# LDO_Schematic.net
KiCad netlist of a schematic drawn in Altium Designer
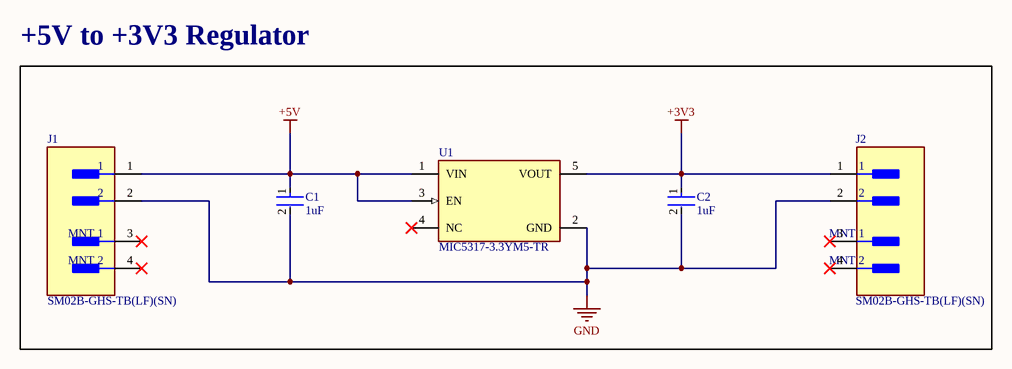
[diagram p0: LDO_Schematic.SchDoc]

(export (version "E")
  (design (tool "Eeschema 10.0.6"))
  (components
    (comp (ref "C1")
      (value "1uF")
      (footprint "FP-CC0805-0_85-MFG")
      (description "CAP CER 1UF 10V X7R 0805")
      (fields
        (field (name "MANUFACTURER") "Yageo")
        (field (name "OCTOPART") "https://octopart.com/cc0805kkx7r6bb105-yageo-42522859")
      )
      (libsource (lib "Altium Content Vault") (part "11868f565c42a9108669ba33697ecf6"))
    )
    (comp (ref "C2")
      (value "1uF")
      (footprint "FP-CC0805-0_85-MFG")
      (description "CAP CER 1UF 10V X7R 0805")
      (fields
        (field (name "MANUFACTURER") "Yageo")
        (field (name "OCTOPART") "https://octopart.com/cc0805kkx7r6bb105-yageo-42522859")
      )
      (libsource (lib "Altium Content Vault") (part "11868f565c42a9108669ba33697ecf6"))
    )
    (comp (ref "J1")
      (value "SM02B-GHS-TB(LF)(SN)")
      (footprint "FP-SM02B-GHS-TB_LF_SN-MFG")
      (description "CONN HEADER SMD R/A 2POS 1.25MM")
      (libsource (lib "") (part "56ec3178a87b3978bdc1b3682cd516a_1"))
    )
    (comp (ref "J2")
      (value "SM02B-GHS-TB(LF)(SN)")
      (footprint "FP-SM02B-GHS-TB_LF_SN-MFG")
      (description "CONN HEADER SMD R/A 2POS 1.25MM")
      (libsource (lib "Altium Content Vault") (part "56ec3178a87b3978bdc1b3682cd516a"))
    )
    (comp (ref "U1")
      (value "MIC5317-3.3YM5-TR")
      (footprint "FP-SOT23-5LD-PL-1-MFG")
      (description "IC REG LINEAR 3.3V 150MA SOT23-5")
      (libsource (lib "Altium Content Vault") (part "0a093dae7315cdc977fd108dde87457"))
    )
  )
  (nets
    (net (code "1") (name "+3V3") (class "Default")
      (node (ref "C2") (pin "1") (pinfunction "1_1") (pintype "passive"))
      (node (ref "J2") (pin "1") (pinfunction "1_1") (pintype "passive"))
      (node (ref "U1") (pin "5") (pinfunction "VOUT_5") (pintype "power_in"))
    )
    (net (code "2") (name "+5V") (class "Default")
      (node (ref "C1") (pin "1") (pinfunction "1_1") (pintype "passive"))
      (node (ref "J1") (pin "1") (pinfunction "1_1") (pintype "passive"))
      (node (ref "U1") (pin "1") (pinfunction "VIN_1") (pintype "power_in"))
      (node (ref "U1") (pin "3") (pinfunction "EN_3") (pintype "input"))
    )
    (net (code "3") (name "GND") (class "Default")
      (node (ref "C1") (pin "2") (pinfunction "2_2") (pintype "passive"))
      (node (ref "C2") (pin "2") (pinfunction "2_2") (pintype "passive"))
      (node (ref "J1") (pin "2") (pinfunction "2_2") (pintype "passive"))
      (node (ref "J2") (pin "2") (pinfunction "2_2") (pintype "passive"))
      (node (ref "U1") (pin "2") (pinfunction "GND_2") (pintype "power_in"))
    )
    (net (code "4") (name "unconnected-(J1-MNT_1-Pad3)") (class "Default")
      (node (ref "J1") (pin "3") (pinfunction "MNT_1_3") (pintype "passive+no_connect"))
    )
    (net (code "5") (name "unconnected-(J1-MNT_2-Pad4)") (class "Default")
      (node (ref "J1") (pin "4") (pinfunction "MNT_2_4") (pintype "passive+no_connect"))
    )
    (net (code "6") (name "unconnected-(J2-MNT_1-Pad3)") (class "Default")
      (node (ref "J2") (pin "3") (pinfunction "MNT_1_3") (pintype "passive+no_connect"))
    )
    (net (code "7") (name "unconnected-(J2-MNT_2-Pad4)") (class "Default")
      (node (ref "J2") (pin "4") (pinfunction "MNT_2_4") (pintype "passive+no_connect"))
    )
    (net (code "8") (name "unconnected-(U1-NC-Pad4)") (class "Default")
      (node (ref "U1") (pin "4") (pinfunction "NC_4") (pintype "passive+no_connect"))
    )
  )
)
